# adaptor.net
KiCad netlist of a schematic drawn in EAGLE
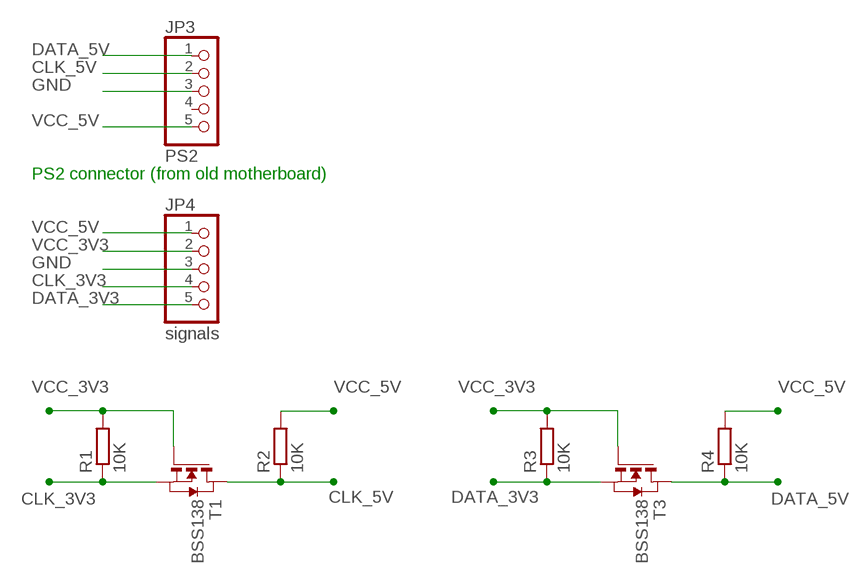
[diagram p0: schematic, sheet 1]

(export (version "E")
  (design (tool "Eeschema 10.0.6"))
  (components
    (comp (ref "JP3")
      (value "PS2")
      (footprint "eagle-import:1X05")
      (libsource (lib "eagle-import") (part "PINHD-1X5"))
    )
    (comp (ref "JP4")
      (value "signals")
      (footprint "eagle-import:1X05")
      (libsource (lib "eagle-import") (part "PINHD-1X5"))
    )
    (comp (ref "R1")
      (value "10K")
      (footprint "eagle-import:R0805")
      (libsource (lib "eagle-import") (part "R-EU_R0805"))
    )
    (comp (ref "R2")
      (value "10K")
      (footprint "eagle-import:R0805")
      (libsource (lib "eagle-import") (part "R-EU_R0805"))
    )
    (comp (ref "R3")
      (value "10K")
      (footprint "eagle-import:R0805")
      (libsource (lib "eagle-import") (part "R-EU_R0805"))
    )
    (comp (ref "R4")
      (value "10K")
      (footprint "eagle-import:R0805")
      (libsource (lib "eagle-import") (part "R-EU_R0805"))
    )
    (comp (ref "T1")
      (value "BSS138")
      (footprint "eagle-import:SOT-23")
      (libsource (lib "eagle-import") (part "NMOSSOT23"))
    )
    (comp (ref "T3")
      (value "BSS138")
      (footprint "eagle-import:SOT-23")
      (libsource (lib "eagle-import") (part "NMOSSOT23"))
    )
  )
  (nets
    (net (code "1") (name "/CLK_3V3") (class "Default")
      (node (ref "JP4") (pin "4") (pinfunction "4_4") (pintype "passive"))
      (node (ref "R1") (pin "1") (pinfunction "1_1") (pintype "passive"))
      (node (ref "T1") (pin "2") (pinfunction "S_2") (pintype "passive"))
    )
    (net (code "2") (name "/CLK_5V") (class "Default")
      (node (ref "JP3") (pin "2") (pinfunction "2_2") (pintype "passive"))
      (node (ref "R2") (pin "1") (pinfunction "1_1") (pintype "passive"))
      (node (ref "T1") (pin "1") (pinfunction "D_1") (pintype "passive"))
    )
    (net (code "3") (name "/DATA_3V3") (class "Default")
      (node (ref "JP4") (pin "5") (pinfunction "5_5") (pintype "passive"))
      (node (ref "R3") (pin "1") (pinfunction "1_1") (pintype "passive"))
      (node (ref "T3") (pin "2") (pinfunction "S_2") (pintype "passive"))
    )
    (net (code "4") (name "/DATA_5V") (class "Default")
      (node (ref "JP3") (pin "1") (pinfunction "1_1") (pintype "passive"))
      (node (ref "R4") (pin "1") (pinfunction "1_1") (pintype "passive"))
      (node (ref "T3") (pin "1") (pinfunction "D_1") (pintype "passive"))
    )
    (net (code "5") (name "/GND") (class "Default")
      (node (ref "JP3") (pin "3") (pinfunction "3_3") (pintype "passive"))
      (node (ref "JP4") (pin "3") (pinfunction "3_3") (pintype "passive"))
    )
    (net (code "6") (name "/VCC_3V3") (class "Default")
      (node (ref "JP4") (pin "2") (pinfunction "2_2") (pintype "passive"))
      (node (ref "R1") (pin "2") (pinfunction "2_2") (pintype "passive"))
      (node (ref "R3") (pin "2") (pinfunction "2_2") (pintype "passive"))
      (node (ref "T1") (pin "3") (pinfunction "G_3") (pintype "passive"))
      (node (ref "T3") (pin "3") (pinfunction "G_3") (pintype "passive"))
    )
    (net (code "7") (name "/VCC_5V") (class "Default")
      (node (ref "JP3") (pin "5") (pinfunction "5_5") (pintype "passive"))
      (node (ref "JP4") (pin "1") (pinfunction "1_1") (pintype "passive"))
      (node (ref "R2") (pin "2") (pinfunction "2_2") (pintype "passive"))
      (node (ref "R4") (pin "2") (pinfunction "2_2") (pintype "passive"))
    )
    (net (code "8") (name "unconnected-(JP3-Pad4)") (class "Default")
      (node (ref "JP3") (pin "4") (pinfunction "4_4") (pintype "passive"))
    )
  )
)
